# Keyboard.net
KiCad netlist of a schematic drawn in Altium Designer
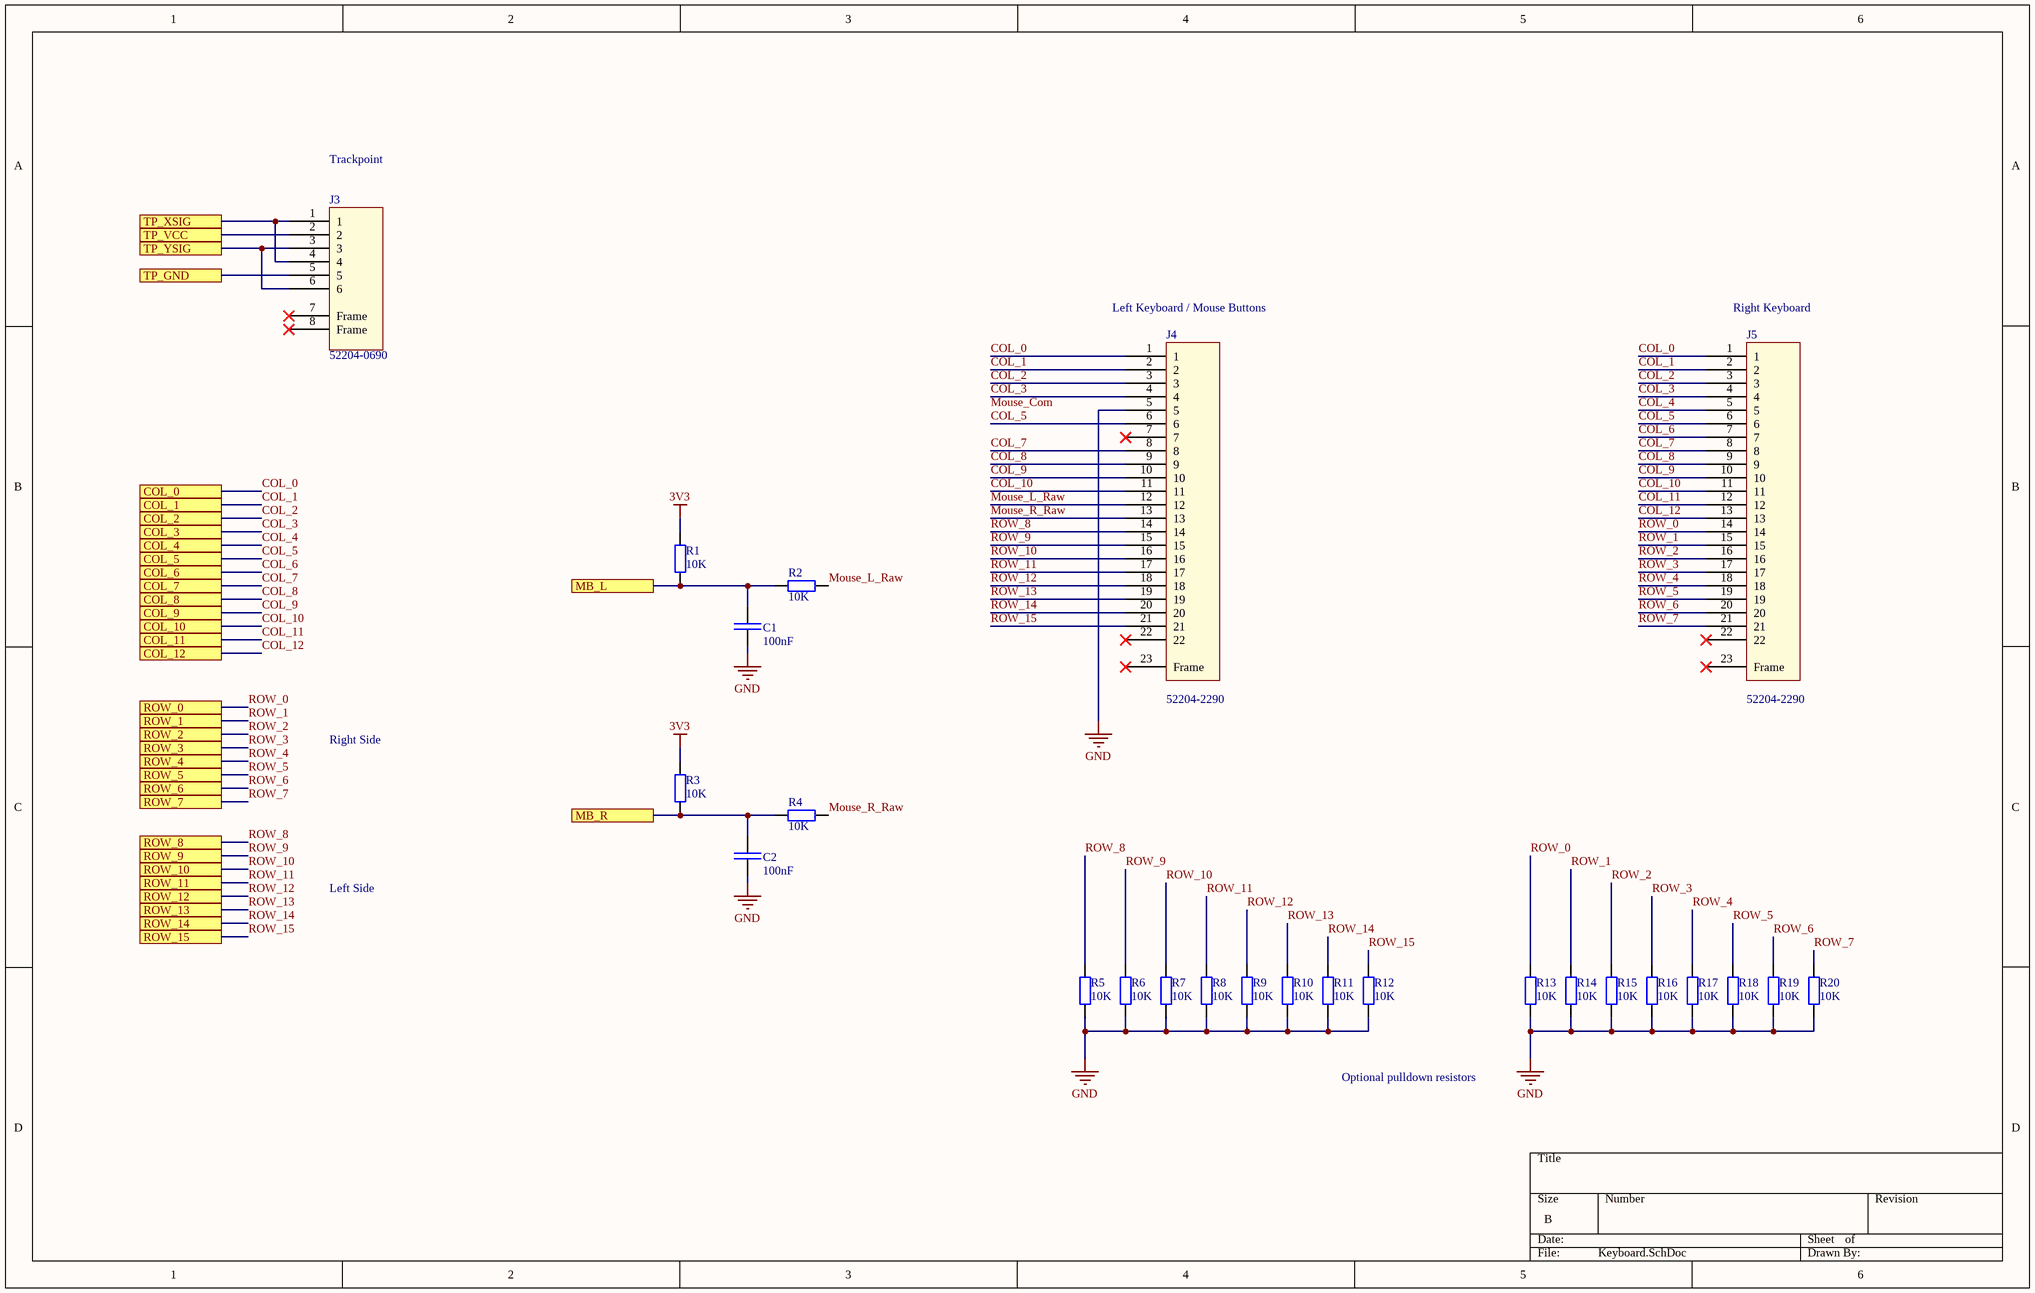
[diagram p0: Keyboard.SchDoc]

(export (version "E")
  (design (tool "Eeschema 10.0.6"))
  (components
    (comp (ref "C1")
      (value "100nF")
      (footprint "CAP_SM0603_YAGEOCC2_N")
      (description "CAP 100nF SM0603 X7R 50V YAGEO CC2")
      (fields
        (field (name "MANUFACTURER") "Yageo")
        (field (name "MANUFACTURER PART NUMBER") "CC0603KRX7R9BB104")
      )
      (libsource (lib "Yageo") (part "CC0603KRX7R9BB104"))
    )
    (comp (ref "C2")
      (value "100nF")
      (footprint "CAP_SM0603_YAGEOCC2_N")
      (description "CAP 100nF SM0603 X7R 50V YAGEO CC2")
      (fields
        (field (name "MANUFACTURER") "Yageo")
        (field (name "MANUFACTURER PART NUMBER") "CC0603KRX7R9BB104")
      )
      (libsource (lib "Yageo") (part "CC0603KRX7R9BB104"))
    )
    (comp (ref "J3")
      (value "52204-0690")
      (footprint "52204-0690")
      (libsource (lib "KBuchka-IntLib") (part "52204-0690"))
    )
    (comp (ref "J4")
      (value "52204-2290")
      (footprint "52204-2290")
      (libsource (lib "KBuchka-IntLib") (part "52204-2290"))
    )
    (comp (ref "J5")
      (value "52204-2290")
      (footprint "52204-2290")
      (libsource (lib "KBuchka-IntLib") (part "52204-2290"))
    )
    (comp (ref "R1")
      (value "10K")
      (footprint "RES_SM0603_YAGEORC_N")
      (description "RES 10K SM0603 YAGEO RC_L")
      (fields
        (field (name "MANUFACTURER") "Yageo")
        (field (name "MANUFACTURER PART NUMBER") "RC0603FR-0710KL")
      )
      (libsource (lib "Yageo") (part "RC0603FR-0710KL"))
    )
    (comp (ref "R2")
      (value "10K")
      (footprint "RES_SM0603_YAGEORC_N")
      (description "RES 10K SM0603 YAGEO RC_L")
      (fields
        (field (name "MANUFACTURER") "Yageo")
        (field (name "MANUFACTURER PART NUMBER") "RC0603FR-0710KL")
      )
      (libsource (lib "") (part "RC0603FR-0710KL_1"))
    )
    (comp (ref "R3")
      (value "10K")
      (footprint "RES_SM0603_YAGEORC_N")
      (description "RES 10K SM0603 YAGEO RC_L")
      (fields
        (field (name "MANUFACTURER") "Yageo")
        (field (name "MANUFACTURER PART NUMBER") "RC0603FR-0710KL")
      )
      (libsource (lib "Yageo") (part "RC0603FR-0710KL"))
    )
    (comp (ref "R4")
      (value "10K")
      (footprint "RES_SM0603_YAGEORC_N")
      (description "RES 10K SM0603 YAGEO RC_L")
      (fields
        (field (name "MANUFACTURER") "Yageo")
        (field (name "MANUFACTURER PART NUMBER") "RC0603FR-0710KL")
      )
      (libsource (lib "") (part "RC0603FR-0710KL_1"))
    )
    (comp (ref "R5")
      (value "10K")
      (footprint "RES_SM0603_YAGEORC_N")
      (description "RES 10K SM0603 YAGEO RC_L")
      (fields
        (field (name "MANUFACTURER") "Yageo")
        (field (name "MANUFACTURER PART NUMBER") "RC0603FR-0710KL")
      )
      (libsource (lib "Yageo") (part "RC0603FR-0710KL"))
    )
    (comp (ref "R6")
      (value "10K")
      (footprint "RES_SM0603_YAGEORC_N")
      (description "RES 10K SM0603 YAGEO RC_L")
      (fields
        (field (name "MANUFACTURER") "Yageo")
        (field (name "MANUFACTURER PART NUMBER") "RC0603FR-0710KL")
      )
      (libsource (lib "Yageo") (part "RC0603FR-0710KL"))
    )
    (comp (ref "R7")
      (value "10K")
      (footprint "RES_SM0603_YAGEORC_N")
      (description "RES 10K SM0603 YAGEO RC_L")
      (fields
        (field (name "MANUFACTURER") "Yageo")
        (field (name "MANUFACTURER PART NUMBER") "RC0603FR-0710KL")
      )
      (libsource (lib "Yageo") (part "RC0603FR-0710KL"))
    )
    (comp (ref "R8")
      (value "10K")
      (footprint "RES_SM0603_YAGEORC_N")
      (description "RES 10K SM0603 YAGEO RC_L")
      (fields
        (field (name "MANUFACTURER") "Yageo")
        (field (name "MANUFACTURER PART NUMBER") "RC0603FR-0710KL")
      )
      (libsource (lib "Yageo") (part "RC0603FR-0710KL"))
    )
    (comp (ref "R9")
      (value "10K")
      (footprint "RES_SM0603_YAGEORC_N")
      (description "RES 10K SM0603 YAGEO RC_L")
      (fields
        (field (name "MANUFACTURER") "Yageo")
        (field (name "MANUFACTURER PART NUMBER") "RC0603FR-0710KL")
      )
      (libsource (lib "Yageo") (part "RC0603FR-0710KL"))
    )
    (comp (ref "R10")
      (value "10K")
      (footprint "RES_SM0603_YAGEORC_N")
      (description "RES 10K SM0603 YAGEO RC_L")
      (fields
        (field (name "MANUFACTURER") "Yageo")
        (field (name "MANUFACTURER PART NUMBER") "RC0603FR-0710KL")
      )
      (libsource (lib "Yageo") (part "RC0603FR-0710KL"))
    )
    (comp (ref "R11")
      (value "10K")
      (footprint "RES_SM0603_YAGEORC_N")
      (description "RES 10K SM0603 YAGEO RC_L")
      (fields
        (field (name "MANUFACTURER") "Yageo")
        (field (name "MANUFACTURER PART NUMBER") "RC0603FR-0710KL")
      )
      (libsource (lib "Yageo") (part "RC0603FR-0710KL"))
    )
    (comp (ref "R12")
      (value "10K")
      (footprint "RES_SM0603_YAGEORC_N")
      (description "RES 10K SM0603 YAGEO RC_L")
      (fields
        (field (name "MANUFACTURER") "Yageo")
        (field (name "MANUFACTURER PART NUMBER") "RC0603FR-0710KL")
      )
      (libsource (lib "Yageo") (part "RC0603FR-0710KL"))
    )
    (comp (ref "R13")
      (value "10K")
      (footprint "RES_SM0603_YAGEORC_N")
      (description "RES 10K SM0603 YAGEO RC_L")
      (fields
        (field (name "MANUFACTURER") "Yageo")
        (field (name "MANUFACTURER PART NUMBER") "RC0603FR-0710KL")
      )
      (libsource (lib "Yageo") (part "RC0603FR-0710KL"))
    )
    (comp (ref "R14")
      (value "10K")
      (footprint "RES_SM0603_YAGEORC_N")
      (description "RES 10K SM0603 YAGEO RC_L")
      (fields
        (field (name "MANUFACTURER") "Yageo")
        (field (name "MANUFACTURER PART NUMBER") "RC0603FR-0710KL")
      )
      (libsource (lib "Yageo") (part "RC0603FR-0710KL"))
    )
    (comp (ref "R15")
      (value "10K")
      (footprint "RES_SM0603_YAGEORC_N")
      (description "RES 10K SM0603 YAGEO RC_L")
      (fields
        (field (name "MANUFACTURER") "Yageo")
        (field (name "MANUFACTURER PART NUMBER") "RC0603FR-0710KL")
      )
      (libsource (lib "Yageo") (part "RC0603FR-0710KL"))
    )
    (comp (ref "R16")
      (value "10K")
      (footprint "RES_SM0603_YAGEORC_N")
      (description "RES 10K SM0603 YAGEO RC_L")
      (fields
        (field (name "MANUFACTURER") "Yageo")
        (field (name "MANUFACTURER PART NUMBER") "RC0603FR-0710KL")
      )
      (libsource (lib "Yageo") (part "RC0603FR-0710KL"))
    )
    (comp (ref "R17")
      (value "10K")
      (footprint "RES_SM0603_YAGEORC_N")
      (description "RES 10K SM0603 YAGEO RC_L")
      (fields
        (field (name "MANUFACTURER") "Yageo")
        (field (name "MANUFACTURER PART NUMBER") "RC0603FR-0710KL")
      )
      (libsource (lib "Yageo") (part "RC0603FR-0710KL"))
    )
    (comp (ref "R18")
      (value "10K")
      (footprint "RES_SM0603_YAGEORC_N")
      (description "RES 10K SM0603 YAGEO RC_L")
      (fields
        (field (name "MANUFACTURER") "Yageo")
        (field (name "MANUFACTURER PART NUMBER") "RC0603FR-0710KL")
      )
      (libsource (lib "Yageo") (part "RC0603FR-0710KL"))
    )
    (comp (ref "R19")
      (value "10K")
      (footprint "RES_SM0603_YAGEORC_N")
      (description "RES 10K SM0603 YAGEO RC_L")
      (fields
        (field (name "MANUFACTURER") "Yageo")
        (field (name "MANUFACTURER PART NUMBER") "RC0603FR-0710KL")
      )
      (libsource (lib "Yageo") (part "RC0603FR-0710KL"))
    )
    (comp (ref "R20")
      (value "10K")
      (footprint "RES_SM0603_YAGEORC_N")
      (description "RES 10K SM0603 YAGEO RC_L")
      (fields
        (field (name "MANUFACTURER") "Yageo")
        (field (name "MANUFACTURER PART NUMBER") "RC0603FR-0710KL")
      )
      (libsource (lib "Yageo") (part "RC0603FR-0710KL"))
    )
  )
  (nets
    (net (code "1") (name "/COL_0") (class "Default")
      (node (ref "J4") (pin "1") (pinfunction "1_1") (pintype "passive"))
      (node (ref "J5") (pin "1") (pinfunction "1_1") (pintype "passive"))
    )
    (net (code "2") (name "/COL_1") (class "Default")
      (node (ref "J4") (pin "2") (pinfunction "2_2") (pintype "passive"))
      (node (ref "J5") (pin "2") (pinfunction "2_2") (pintype "passive"))
    )
    (net (code "3") (name "/COL_2") (class "Default")
      (node (ref "J4") (pin "3") (pinfunction "3_3") (pintype "passive"))
      (node (ref "J5") (pin "3") (pinfunction "3_3") (pintype "passive"))
    )
    (net (code "4") (name "/COL_3") (class "Default")
      (node (ref "J4") (pin "4") (pinfunction "4_4") (pintype "passive"))
      (node (ref "J5") (pin "4") (pinfunction "4_4") (pintype "passive"))
    )
    (net (code "5") (name "/COL_4") (class "Default")
      (node (ref "J5") (pin "5") (pinfunction "5_5") (pintype "passive"))
    )
    (net (code "6") (name "/COL_5") (class "Default")
      (node (ref "J4") (pin "6") (pinfunction "6_6") (pintype "passive"))
      (node (ref "J5") (pin "6") (pinfunction "6_6") (pintype "passive"))
    )
    (net (code "7") (name "/COL_6") (class "Default")
      (node (ref "J5") (pin "7") (pinfunction "7_7") (pintype "passive"))
    )
    (net (code "8") (name "/COL_7") (class "Default")
      (node (ref "J4") (pin "8") (pinfunction "8_8") (pintype "passive"))
      (node (ref "J5") (pin "8") (pinfunction "8_8") (pintype "passive"))
    )
    (net (code "9") (name "/COL_8") (class "Default")
      (node (ref "J4") (pin "9") (pinfunction "9_9") (pintype "passive"))
      (node (ref "J5") (pin "9") (pinfunction "9_9") (pintype "passive"))
    )
    (net (code "10") (name "/COL_9") (class "Default")
      (node (ref "J4") (pin "10") (pinfunction "10_10") (pintype "passive"))
      (node (ref "J5") (pin "10") (pinfunction "10_10") (pintype "passive"))
    )
    (net (code "11") (name "/COL_10") (class "Default")
      (node (ref "J4") (pin "11") (pinfunction "11_11") (pintype "passive"))
      (node (ref "J5") (pin "11") (pinfunction "11_11") (pintype "passive"))
    )
    (net (code "12") (name "/COL_11") (class "Default")
      (node (ref "J5") (pin "12") (pinfunction "12_12") (pintype "passive"))
    )
    (net (code "13") (name "/COL_12") (class "Default")
      (node (ref "J5") (pin "13") (pinfunction "13_13") (pintype "passive"))
    )
    (net (code "14") (name "/MB_L") (class "Default")
      (node (ref "C1") (pin "2") (pintype "passive"))
      (node (ref "R1") (pin "2") (pintype "passive"))
      (node (ref "R2") (pin "2") (pintype "passive"))
    )
    (net (code "15") (name "/MB_R") (class "Default")
      (node (ref "C2") (pin "2") (pintype "passive"))
      (node (ref "R3") (pin "2") (pintype "passive"))
      (node (ref "R4") (pin "2") (pintype "passive"))
    )
    (net (code "17") (name "/Mouse_L_Raw") (class "Default")
      (node (ref "J4") (pin "12") (pinfunction "12_12") (pintype "passive"))
      (node (ref "R2") (pin "1") (pintype "passive"))
    )
    (net (code "18") (name "/Mouse_R_Raw") (class "Default")
      (node (ref "J4") (pin "13") (pinfunction "13_13") (pintype "passive"))
      (node (ref "R4") (pin "1") (pintype "passive"))
    )
    (net (code "19") (name "/ROW_0") (class "Default")
      (node (ref "J5") (pin "14") (pinfunction "14_14") (pintype "passive"))
      (node (ref "R13") (pin "1") (pintype "passive"))
    )
    (net (code "20") (name "/ROW_1") (class "Default")
      (node (ref "J5") (pin "15") (pinfunction "15_15") (pintype "passive"))
      (node (ref "R14") (pin "1") (pintype "passive"))
    )
    (net (code "21") (name "/ROW_2") (class "Default")
      (node (ref "J5") (pin "16") (pinfunction "16_16") (pintype "passive"))
      (node (ref "R15") (pin "1") (pintype "passive"))
    )
    (net (code "22") (name "/ROW_3") (class "Default")
      (node (ref "J5") (pin "17") (pinfunction "17_17") (pintype "passive"))
      (node (ref "R16") (pin "1") (pintype "passive"))
    )
    (net (code "23") (name "/ROW_4") (class "Default")
      (node (ref "J5") (pin "18") (pinfunction "18_18") (pintype "passive"))
      (node (ref "R17") (pin "1") (pintype "passive"))
    )
    (net (code "24") (name "/ROW_5") (class "Default")
      (node (ref "J5") (pin "19") (pinfunction "19_19") (pintype "passive"))
      (node (ref "R18") (pin "1") (pintype "passive"))
    )
    (net (code "25") (name "/ROW_6") (class "Default")
      (node (ref "J5") (pin "20") (pinfunction "20_20") (pintype "passive"))
      (node (ref "R19") (pin "1") (pintype "passive"))
    )
    (net (code "26") (name "/ROW_7") (class "Default")
      (node (ref "J5") (pin "21") (pinfunction "21_21") (pintype "passive"))
      (node (ref "R20") (pin "1") (pintype "passive"))
    )
    (net (code "27") (name "/ROW_8") (class "Default")
      (node (ref "J4") (pin "14") (pinfunction "14_14") (pintype "passive"))
      (node (ref "R5") (pin "1") (pintype "passive"))
    )
    (net (code "28") (name "/ROW_9") (class "Default")
      (node (ref "J4") (pin "15") (pinfunction "15_15") (pintype "passive"))
      (node (ref "R6") (pin "1") (pintype "passive"))
    )
    (net (code "29") (name "/ROW_10") (class "Default")
      (node (ref "J4") (pin "16") (pinfunction "16_16") (pintype "passive"))
      (node (ref "R7") (pin "1") (pintype "passive"))
    )
    (net (code "30") (name "/ROW_11") (class "Default")
      (node (ref "J4") (pin "17") (pinfunction "17_17") (pintype "passive"))
      (node (ref "R8") (pin "1") (pintype "passive"))
    )
    (net (code "31") (name "/ROW_12") (class "Default")
      (node (ref "J4") (pin "18") (pinfunction "18_18") (pintype "passive"))
      (node (ref "R9") (pin "1") (pintype "passive"))
    )
    (net (code "32") (name "/ROW_13") (class "Default")
      (node (ref "J4") (pin "19") (pinfunction "19_19") (pintype "passive"))
      (node (ref "R10") (pin "1") (pintype "passive"))
    )
    (net (code "33") (name "/ROW_14") (class "Default")
      (node (ref "J4") (pin "20") (pinfunction "20_20") (pintype "passive"))
      (node (ref "R11") (pin "1") (pintype "passive"))
    )
    (net (code "34") (name "/ROW_15") (class "Default")
      (node (ref "J4") (pin "21") (pinfunction "21_21") (pintype "passive"))
      (node (ref "R12") (pin "1") (pintype "passive"))
    )
    (net (code "35") (name "/TP_GND") (class "Default")
      (node (ref "J3") (pin "5") (pinfunction "5_5") (pintype "passive"))
    )
    (net (code "36") (name "/TP_VCC") (class "Default")
      (node (ref "J3") (pin "2") (pinfunction "2_2") (pintype "passive"))
    )
    (net (code "37") (name "/TP_XSIG") (class "Default")
      (node (ref "J3") (pin "1") (pinfunction "1_1") (pintype "passive"))
      (node (ref "J3") (pin "4") (pinfunction "4_4") (pintype "passive"))
    )
    (net (code "38") (name "/TP_YSIG") (class "Default")
      (node (ref "J3") (pin "3") (pinfunction "3_3") (pintype "passive"))
      (node (ref "J3") (pin "6") (pinfunction "6_6") (pintype "passive"))
    )
    (net (code "39") (name "3V3") (class "Default")
      (node (ref "R1") (pin "1") (pintype "passive"))
      (node (ref "R3") (pin "1") (pintype "passive"))
    )
    (net (code "40") (name "GND") (class "Default")
      (node (ref "C1") (pin "1") (pintype "passive"))
      (node (ref "C2") (pin "1") (pintype "passive"))
      (node (ref "J4") (pin "5") (pinfunction "5_5") (pintype "passive"))
      (node (ref "R10") (pin "2") (pintype "passive"))
      (node (ref "R11") (pin "2") (pintype "passive"))
      (node (ref "R12") (pin "2") (pintype "passive"))
      (node (ref "R13") (pin "2") (pintype "passive"))
      (node (ref "R14") (pin "2") (pintype "passive"))
      (node (ref "R15") (pin "2") (pintype "passive"))
      (node (ref "R16") (pin "2") (pintype "passive"))
      (node (ref "R17") (pin "2") (pintype "passive"))
      (node (ref "R18") (pin "2") (pintype "passive"))
      (node (ref "R19") (pin "2") (pintype "passive"))
      (node (ref "R20") (pin "2") (pintype "passive"))
      (node (ref "R5") (pin "2") (pintype "passive"))
      (node (ref "R6") (pin "2") (pintype "passive"))
      (node (ref "R7") (pin "2") (pintype "passive"))
      (node (ref "R8") (pin "2") (pintype "passive"))
      (node (ref "R9") (pin "2") (pintype "passive"))
    )
    (net (code "41") (name "unconnected-(J3-Frame-Pad7)") (class "Default")
      (node (ref "J3") (pin "7") (pinfunction "Frame_7") (pintype "passive+no_connect"))
    )
    (net (code "42") (name "unconnected-(J3-Frame-Pad8)") (class "Default")
      (node (ref "J3") (pin "8") (pinfunction "Frame_8") (pintype "passive+no_connect"))
    )
    (net (code "43") (name "unconnected-(J4-Frame-Pad23)") (class "Default")
      (node (ref "J4") (pin "23") (pinfunction "Frame_23") (pintype "passive+no_connect"))
    )
    (net (code "44") (name "unconnected-(J4-Pad7)") (class "Default")
      (node (ref "J4") (pin "7") (pinfunction "7_7") (pintype "passive+no_connect"))
    )
    (net (code "45") (name "unconnected-(J4-Pad22)") (class "Default")
      (node (ref "J4") (pin "22") (pinfunction "22_22") (pintype "passive+no_connect"))
    )
    (net (code "46") (name "unconnected-(J5-Frame-Pad23)") (class "Default")
      (node (ref "J5") (pin "23") (pinfunction "Frame_23") (pintype "passive+no_connect"))
    )
    (net (code "47") (name "unconnected-(J5-Pad22)") (class "Default")
      (node (ref "J5") (pin "22") (pinfunction "22_22") (pintype "passive+no_connect"))
    )
  )
)
